# Sheet1.net
KiCad netlist of a schematic drawn in Altium Designer
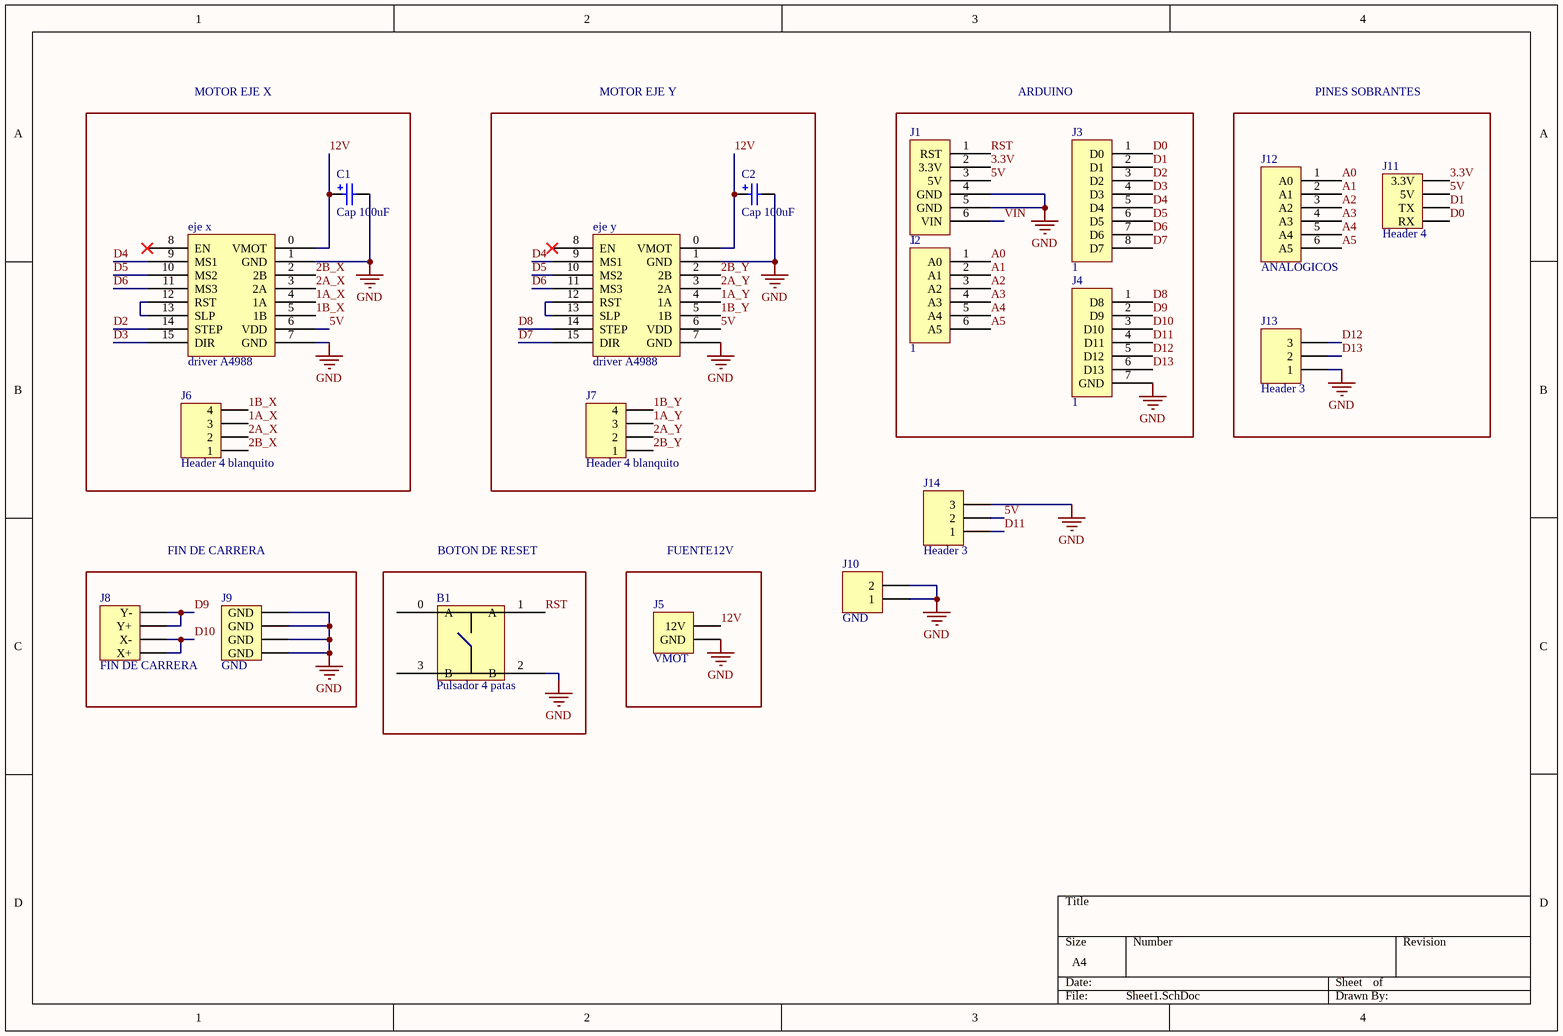
[diagram p0: Sheet1.SchDoc]

(export (version "E")
  (design (tool "Eeschema 10.0.6"))
  (components
    (comp (ref "B1")
      (value "Pulsador 4 patas")
      (footprint "Pulsador4patas")
      (libsource (lib "BARTELLONE") (part "Pulsador 4 patas"))
    )
    (comp (ref "C1")
      (value "Cap 100uF")
      (footprint "Cap 100uF 50V")
      (description "Polarized Capacitor (Radial)")
      (fields (field (name "PUBLISHER") "Altium Limited"))
      (libsource (lib "BARTELLONE") (part "Cap 100uF 50V"))
    )
    (comp (ref "C2")
      (value "Cap 100uF")
      (footprint "Cap 100uF 50V")
      (description "Polarized Capacitor (Radial)")
      (fields (field (name "PUBLISHER") "Altium Limited"))
      (libsource (lib "BARTELLONE") (part "Cap 100uF 50V"))
    )
    (comp (ref "eje x")
      (value "driver A4988")
      (footprint "DRIVER A4988")
      (libsource (lib "BARTELLONE") (part "driver A4988"))
    )
    (comp (ref "eje y")
      (value "driver A4988")
      (footprint "DRIVER A4988")
      (libsource (lib "BARTELLONE") (part "driver A4988"))
    )
    (comp (ref "J1") (value "1") (footprint "HDR1X6") (libsource (lib "BARTELLONE") (part "header X6")))
    (comp (ref "J2") (value "1") (footprint "HDR1X6") (libsource (lib "BARTELLONE") (part "header X6")))
    (comp (ref "J3") (value "1") (footprint "HDR1X8") (libsource (lib "BARTELLONE") (part "header X8")))
    (comp (ref "J4") (value "1") (footprint "HDR1X7") (libsource (lib "BARTELLONE") (part "header X7")))
    (comp (ref "J5")
      (value "VMOT")
      (footprint "Bornerax2")
      (description "Header, 2-Pin")
      (fields (field (name "PUBLISHER") "Altium Limited"))
      (libsource (lib "BARTELLONE") (part "Bornerax2"))
    )
    (comp (ref "J6")
      (value "Header 4 blanquito")
      (footprint "HDR1X4 blanquito")
      (description "Header, 2-Pin")
      (fields (field (name "PUBLISHER") "Altium Limited"))
      (libsource (lib "BARTELLONE") (part "Header 4_1"))
    )
    (comp (ref "J7")
      (value "Header 4 blanquito")
      (footprint "HDR1X4 blanquito")
      (description "Header, 2-Pin")
      (fields (field (name "PUBLISHER") "Altium Limited"))
      (libsource (lib "BARTELLONE") (part "Header 4_1"))
    )
    (comp (ref "J8")
      (value "FIN DE CARRERA")
      (footprint "HDR1X4")
      (description "Header, 2-Pin")
      (fields (field (name "PUBLISHER") "Altium Limited"))
      (libsource (lib "BARTELLONE") (part "Header 4"))
    )
    (comp (ref "J9")
      (value "GND")
      (footprint "HDR1X4")
      (description "Header, 2-Pin")
      (fields (field (name "PUBLISHER") "Altium Limited"))
      (libsource (lib "BARTELLONE") (part "Header 4"))
    )
    (comp (ref "J10")
      (value "GND")
      (footprint "HDR1X2")
      (description "Header, 2-Pin")
      (fields (field (name "PUBLISHER") "Altium Limited"))
      (libsource (lib "BARTELLONE") (part "Header 2"))
    )
    (comp (ref "J11")
      (value "Header 4")
      (footprint "HDR1X4")
      (description "Header, 2-Pin")
      (fields (field (name "PUBLISHER") "Altium Limited"))
      (libsource (lib "BARTELLONE") (part "Header 4"))
    )
    (comp (ref "J12")
      (value "ANALOGICOS")
      (footprint "HDR1X6")
      (libsource (lib "BARTELLONE") (part "header X6"))
    )
    (comp (ref "J13")
      (value "Header 3")
      (footprint "HDR1X3")
      (description "Header, 3-Pin")
      (fields (field (name "PUBLISHER") "Altium Limited"))
      (libsource (lib "Miscellaneous Connectors") (part "Header 3"))
    )
    (comp (ref "J14")
      (value "Header 3")
      (footprint "HDR1X3")
      (description "Header, 3-Pin")
      (fields (field (name "PUBLISHER") "Altium Limited"))
      (libsource (lib "Miscellaneous Connectors") (part "Header 3"))
    )
  )
  (nets
    (net (code "1") (name "/1A_X") (class "Default")
      (node (ref "J6") (pin "3") (pinfunction "3_3") (pintype "passive"))
      (node (ref "eje x") (pin "4") (pinfunction "1A_4") (pintype "passive"))
    )
    (net (code "2") (name "/1A_Y") (class "Default")
      (node (ref "J7") (pin "3") (pinfunction "3_3") (pintype "passive"))
      (node (ref "eje y") (pin "4") (pinfunction "1A_4") (pintype "passive"))
    )
    (net (code "3") (name "/1B_X") (class "Default")
      (node (ref "J6") (pin "4") (pinfunction "4_4") (pintype "passive"))
      (node (ref "eje x") (pin "5") (pinfunction "1B_5") (pintype "passive"))
    )
    (net (code "4") (name "/1B_Y") (class "Default")
      (node (ref "J7") (pin "4") (pinfunction "4_4") (pintype "passive"))
      (node (ref "eje y") (pin "5") (pinfunction "1B_5") (pintype "passive"))
    )
    (net (code "5") (name "/2A_X") (class "Default")
      (node (ref "J6") (pin "2") (pinfunction "2_2") (pintype "passive"))
      (node (ref "eje x") (pin "3") (pinfunction "2A_3") (pintype "passive"))
    )
    (net (code "6") (name "/2A_Y") (class "Default")
      (node (ref "J7") (pin "2") (pinfunction "2_2") (pintype "passive"))
      (node (ref "eje y") (pin "3") (pinfunction "2A_3") (pintype "passive"))
    )
    (net (code "7") (name "/2B_X") (class "Default")
      (node (ref "J6") (pin "1") (pinfunction "1_1") (pintype "passive"))
      (node (ref "eje x") (pin "2") (pinfunction "2B_2") (pintype "passive"))
    )
    (net (code "8") (name "/2B_Y") (class "Default")
      (node (ref "J7") (pin "1") (pinfunction "1_1") (pintype "passive"))
      (node (ref "eje y") (pin "2") (pinfunction "2B_2") (pintype "passive"))
    )
    (net (code "9") (name "/3.3V") (class "Default")
      (node (ref "J1") (pin "2") (pinfunction "3.3V_2") (pintype "passive"))
      (node (ref "J11") (pin "4") (pinfunction "Y-_4") (pintype "passive"))
    )
    (net (code "10") (name "/5V") (class "Default")
      (node (ref "J1") (pin "3") (pinfunction "5V_3") (pintype "passive"))
      (node (ref "J11") (pin "3") (pinfunction "Y+_3") (pintype "passive"))
      (node (ref "J14") (pin "2") (pinfunction "2_2") (pintype "passive"))
      (node (ref "eje x") (pin "6") (pinfunction "VDD_6") (pintype "passive"))
      (node (ref "eje y") (pin "6") (pinfunction "VDD_6") (pintype "passive"))
    )
    (net (code "11") (name "/12V") (class "Default")
      (node (ref "C1") (pin "1") (pinfunction "1_1") (pintype "passive"))
      (node (ref "C2") (pin "1") (pinfunction "1_1") (pintype "passive"))
      (node (ref "J5") (pin "2") (pinfunction "12V_2") (pintype "passive"))
      (node (ref "eje x") (pin "0") (pinfunction "VMOT_0") (pintype "passive"))
      (node (ref "eje y") (pin "0") (pinfunction "VMOT_0") (pintype "passive"))
    )
    (net (code "12") (name "/A0") (class "Default")
      (node (ref "J12") (pin "1") (pinfunction "RST_1") (pintype "passive"))
      (node (ref "J2") (pin "1") (pinfunction "RST_1") (pintype "passive"))
    )
    (net (code "13") (name "/A1") (class "Default")
      (node (ref "J12") (pin "2") (pinfunction "3.3V_2") (pintype "passive"))
      (node (ref "J2") (pin "2") (pinfunction "3.3V_2") (pintype "passive"))
    )
    (net (code "14") (name "/A2") (class "Default")
      (node (ref "J12") (pin "3") (pinfunction "5V_3") (pintype "passive"))
      (node (ref "J2") (pin "3") (pinfunction "5V_3") (pintype "passive"))
    )
    (net (code "15") (name "/A3") (class "Default")
      (node (ref "J12") (pin "4") (pinfunction "GND_4") (pintype "passive"))
      (node (ref "J2") (pin "4") (pinfunction "GND_4") (pintype "passive"))
    )
    (net (code "16") (name "/A4") (class "Default")
      (node (ref "J12") (pin "5") (pinfunction "GND_5") (pintype "passive"))
      (node (ref "J2") (pin "5") (pinfunction "GND_5") (pintype "passive"))
    )
    (net (code "17") (name "/A5") (class "Default")
      (node (ref "J12") (pin "6") (pinfunction "VIN_6") (pintype "passive"))
      (node (ref "J2") (pin "6") (pinfunction "VIN_6") (pintype "passive"))
    )
    (net (code "18") (name "/D0") (class "Default")
      (node (ref "J11") (pin "1") (pinfunction "X+_1") (pintype "passive"))
      (node (ref "J3") (pin "1") (pinfunction "D0_1") (pintype "passive"))
    )
    (net (code "19") (name "/D1") (class "Default")
      (node (ref "J11") (pin "2") (pinfunction "X-_2") (pintype "passive"))
      (node (ref "J3") (pin "2") (pinfunction "D1_2") (pintype "passive"))
    )
    (net (code "20") (name "/D2") (class "Default")
      (node (ref "J3") (pin "3") (pinfunction "D2_3") (pintype "passive"))
      (node (ref "eje x") (pin "14") (pinfunction "STEP_14") (pintype "passive"))
    )
    (net (code "21") (name "/D3") (class "Default")
      (node (ref "J3") (pin "4") (pinfunction "D3_4") (pintype "passive"))
      (node (ref "eje x") (pin "15") (pinfunction "DIR_15") (pintype "passive"))
    )
    (net (code "22") (name "/D4") (class "Default")
      (node (ref "J3") (pin "5") (pinfunction "D4_5") (pintype "passive"))
      (node (ref "eje x") (pin "9") (pinfunction "MS1_9") (pintype "passive"))
      (node (ref "eje y") (pin "9") (pinfunction "MS1_9") (pintype "passive"))
    )
    (net (code "23") (name "/D5") (class "Default")
      (node (ref "J3") (pin "6") (pinfunction "D5_6") (pintype "passive"))
      (node (ref "eje x") (pin "10") (pinfunction "MS2_10") (pintype "passive"))
      (node (ref "eje y") (pin "10") (pinfunction "MS2_10") (pintype "passive"))
    )
    (net (code "24") (name "/D6") (class "Default")
      (node (ref "J3") (pin "7") (pinfunction "D6_7") (pintype "passive"))
      (node (ref "eje x") (pin "11") (pinfunction "MS3_11") (pintype "passive"))
      (node (ref "eje y") (pin "11") (pinfunction "MS3_11") (pintype "passive"))
    )
    (net (code "25") (name "/D7") (class "Default")
      (node (ref "J3") (pin "8") (pinfunction "D7_8") (pintype "passive"))
      (node (ref "eje y") (pin "15") (pinfunction "DIR_15") (pintype "passive"))
    )
    (net (code "26") (name "/D8") (class "Default")
      (node (ref "J4") (pin "1") (pinfunction "D8_1") (pintype "passive"))
      (node (ref "eje y") (pin "14") (pinfunction "STEP_14") (pintype "passive"))
    )
    (net (code "27") (name "/D9") (class "Default")
      (node (ref "J4") (pin "2") (pinfunction "D9_2") (pintype "passive"))
      (node (ref "J8") (pin "3") (pinfunction "Y+_3") (pintype "passive"))
      (node (ref "J8") (pin "4") (pinfunction "Y-_4") (pintype "passive"))
    )
    (net (code "28") (name "/D10") (class "Default")
      (node (ref "J4") (pin "3") (pinfunction "D10_3") (pintype "passive"))
      (node (ref "J8") (pin "1") (pinfunction "X+_1") (pintype "passive"))
      (node (ref "J8") (pin "2") (pinfunction "X-_2") (pintype "passive"))
    )
    (net (code "29") (name "/D11") (class "Default")
      (node (ref "J14") (pin "1") (pinfunction "1_1") (pintype "passive"))
      (node (ref "J4") (pin "4") (pinfunction "D11_4") (pintype "passive"))
    )
    (net (code "30") (name "/D12") (class "Default")
      (node (ref "J13") (pin "3") (pinfunction "3_3") (pintype "passive"))
      (node (ref "J4") (pin "5") (pinfunction "D12_5") (pintype "passive"))
    )
    (net (code "31") (name "/D13") (class "Default")
      (node (ref "J13") (pin "2") (pinfunction "2_2") (pintype "passive"))
      (node (ref "J4") (pin "6") (pinfunction "D13_6") (pintype "passive"))
    )
    (net (code "32") (name "/RST") (class "Default")
      (node (ref "B1") (pin "1") (pinfunction "A_1") (pintype "passive"))
      (node (ref "J1") (pin "1") (pinfunction "RST_1") (pintype "passive"))
    )
    (net (code "33") (name "/VIN") (class "Default")
      (node (ref "J1") (pin "6") (pinfunction "VIN_6") (pintype "passive"))
    )
    (net (code "34") (name "GND") (class "Default")
      (node (ref "B1") (pin "2") (pinfunction "B_2") (pintype "passive"))
      (node (ref "C1") (pin "2") (pinfunction "2_2") (pintype "passive"))
      (node (ref "C2") (pin "2") (pinfunction "2_2") (pintype "passive"))
      (node (ref "J1") (pin "4") (pinfunction "GND_4") (pintype "passive"))
      (node (ref "J1") (pin "5") (pinfunction "GND_5") (pintype "passive"))
      (node (ref "J10") (pin "1") (pinfunction "1_1") (pintype "passive"))
      (node (ref "J10") (pin "2") (pinfunction "2_2") (pintype "passive"))
      (node (ref "J13") (pin "1") (pinfunction "1_1") (pintype "passive"))
      (node (ref "J14") (pin "3") (pinfunction "3_3") (pintype "passive"))
      (node (ref "J4") (pin "7") (pinfunction "GND_7") (pintype "passive"))
      (node (ref "J5") (pin "1") (pinfunction "GND_1") (pintype "passive"))
      (node (ref "J9") (pin "1") (pinfunction "X+_1") (pintype "passive"))
      (node (ref "J9") (pin "2") (pinfunction "X-_2") (pintype "passive"))
      (node (ref "J9") (pin "3") (pinfunction "Y+_3") (pintype "passive"))
      (node (ref "J9") (pin "4") (pinfunction "Y-_4") (pintype "passive"))
      (node (ref "eje x") (pin "1") (pinfunction "GND_1") (pintype "passive"))
      (node (ref "eje x") (pin "7") (pinfunction "GND_7") (pintype "passive"))
      (node (ref "eje y") (pin "1") (pinfunction "GND_1") (pintype "passive"))
      (node (ref "eje y") (pin "7") (pinfunction "GND_7") (pintype "passive"))
    )
    (net (code "35") (name "Net-(eje x-RST)") (class "Default")
      (node (ref "eje x") (pin "12") (pinfunction "RST_12") (pintype "passive"))
      (node (ref "eje x") (pin "13") (pinfunction "SLP_13") (pintype "passive"))
    )
    (net (code "36") (name "Net-(eje y-RST)") (class "Default")
      (node (ref "eje y") (pin "12") (pinfunction "RST_12") (pintype "passive"))
      (node (ref "eje y") (pin "13") (pinfunction "SLP_13") (pintype "passive"))
    )
    (net (code "37") (name "unconnected-(B1-A-Pad0)") (class "Default")
      (node (ref "B1") (pin "0") (pinfunction "A_0") (pintype "passive"))
    )
    (net (code "38") (name "unconnected-(B1-B-Pad3)") (class "Default")
      (node (ref "B1") (pin "3") (pinfunction "B_3") (pintype "passive"))
    )
    (net (code "39") (name "unconnected-(eje x-EN-Pad8)") (class "Default")
      (node (ref "eje x") (pin "8") (pinfunction "EN_8") (pintype "passive+no_connect"))
    )
    (net (code "40") (name "unconnected-(eje y-EN-Pad8)") (class "Default")
      (node (ref "eje y") (pin "8") (pinfunction "EN_8") (pintype "passive+no_connect"))
    )
  )
)
